# Bordnetzwandler.net
KiCad netlist of a schematic drawn in EAGLE
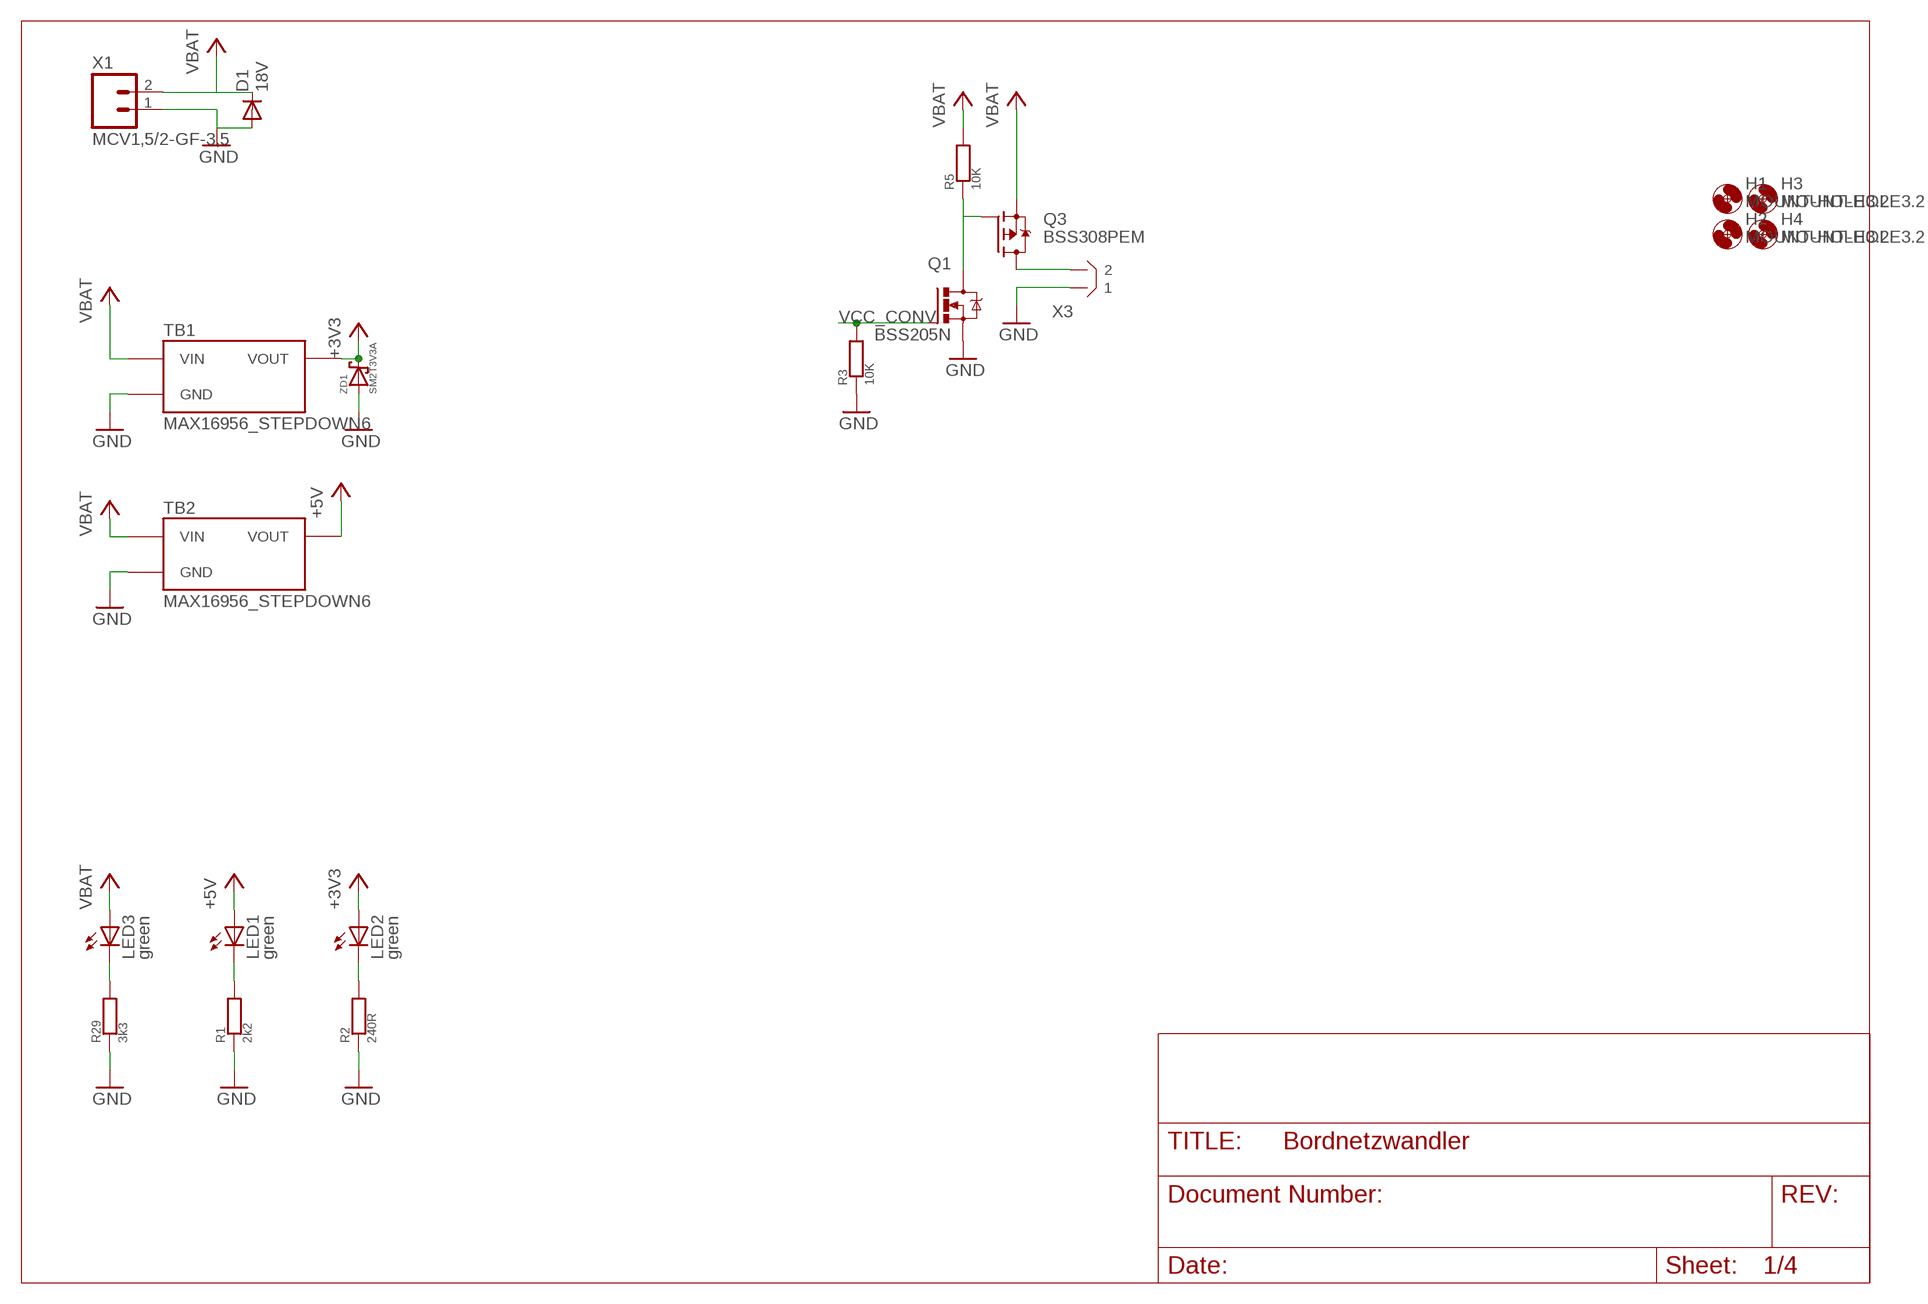
[diagram p0: schematic, sheet 1]
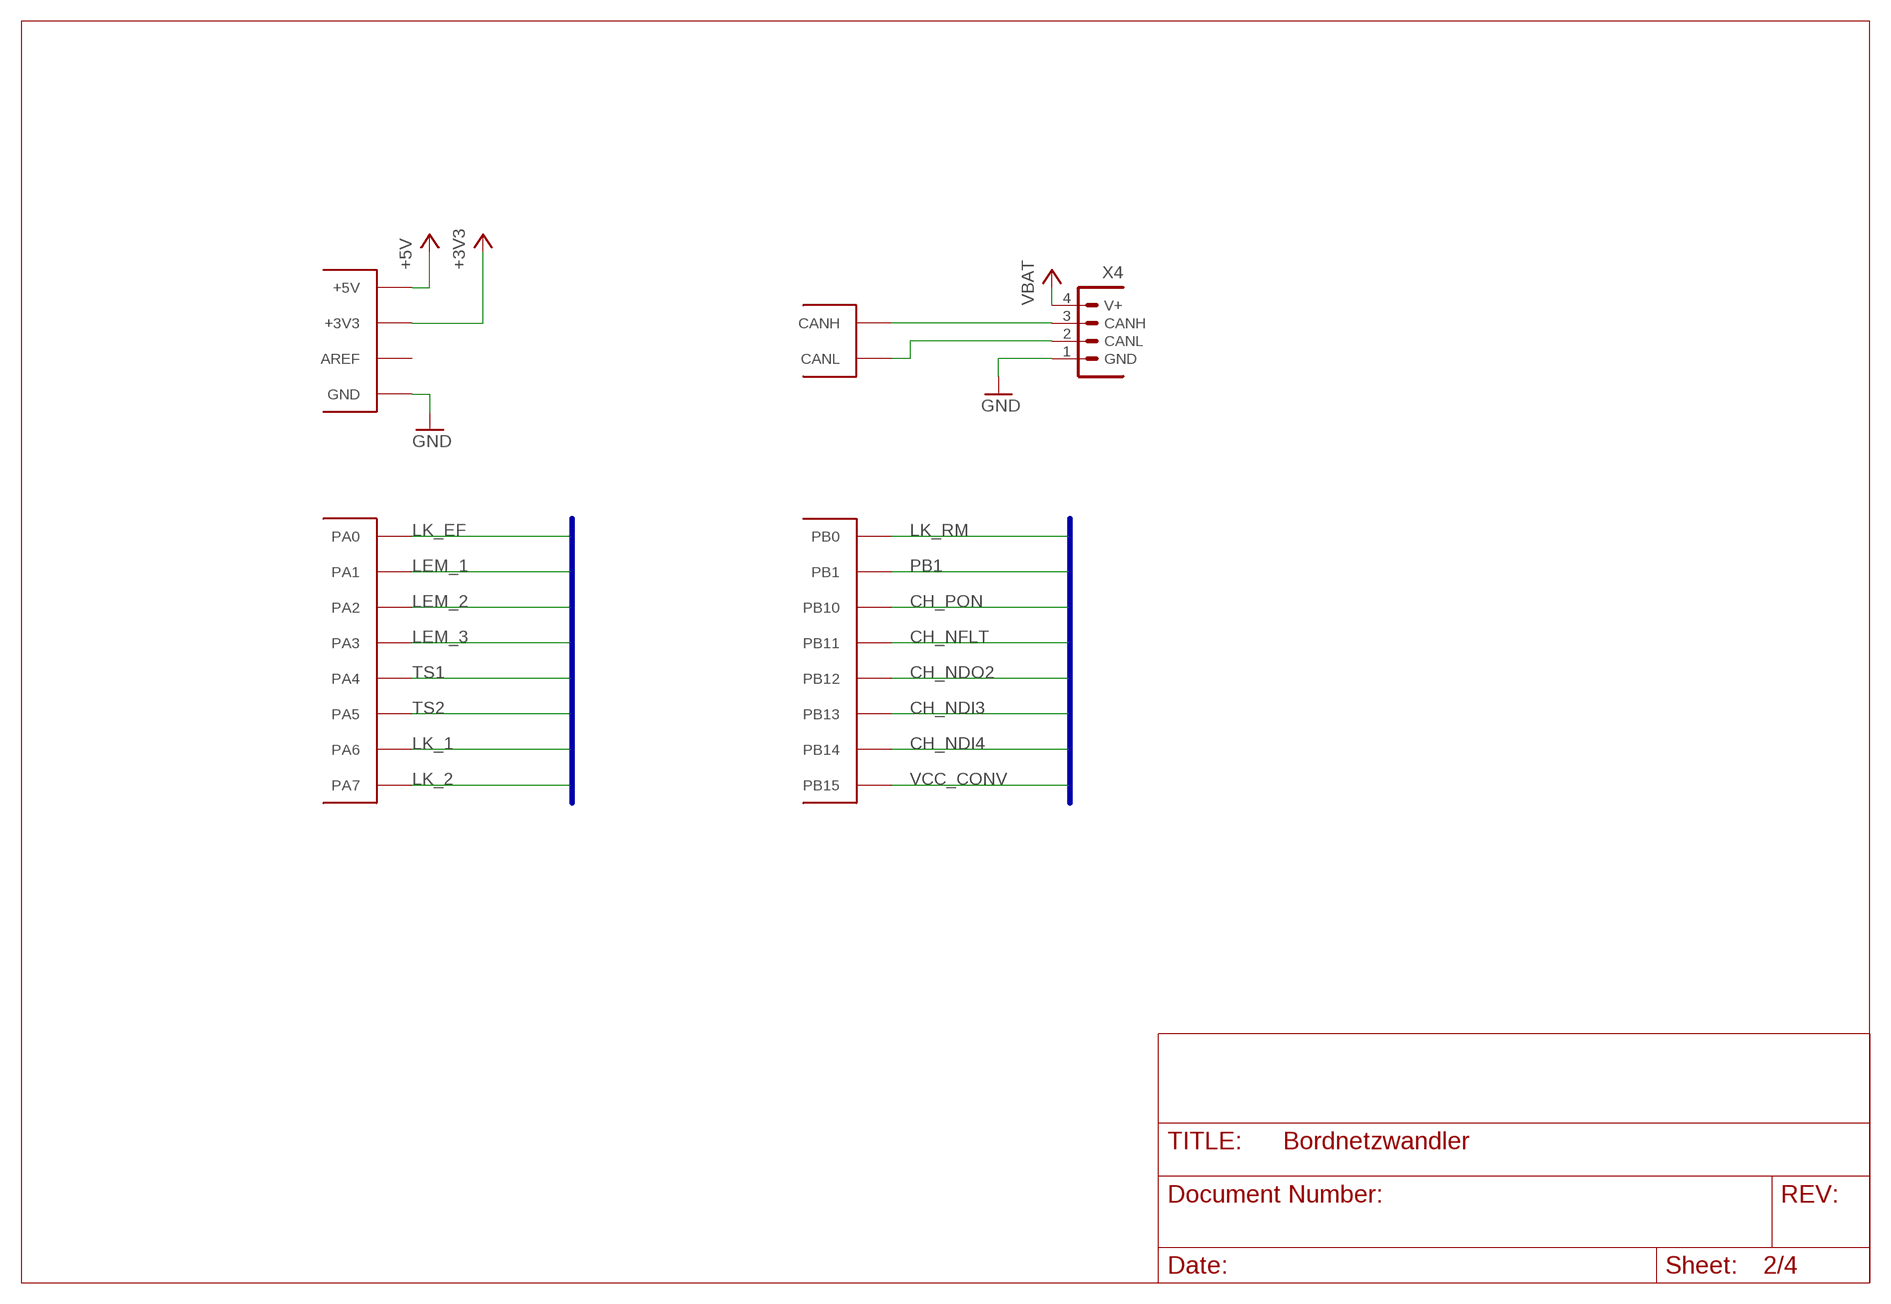
[diagram p1: schematic, sheet 2]
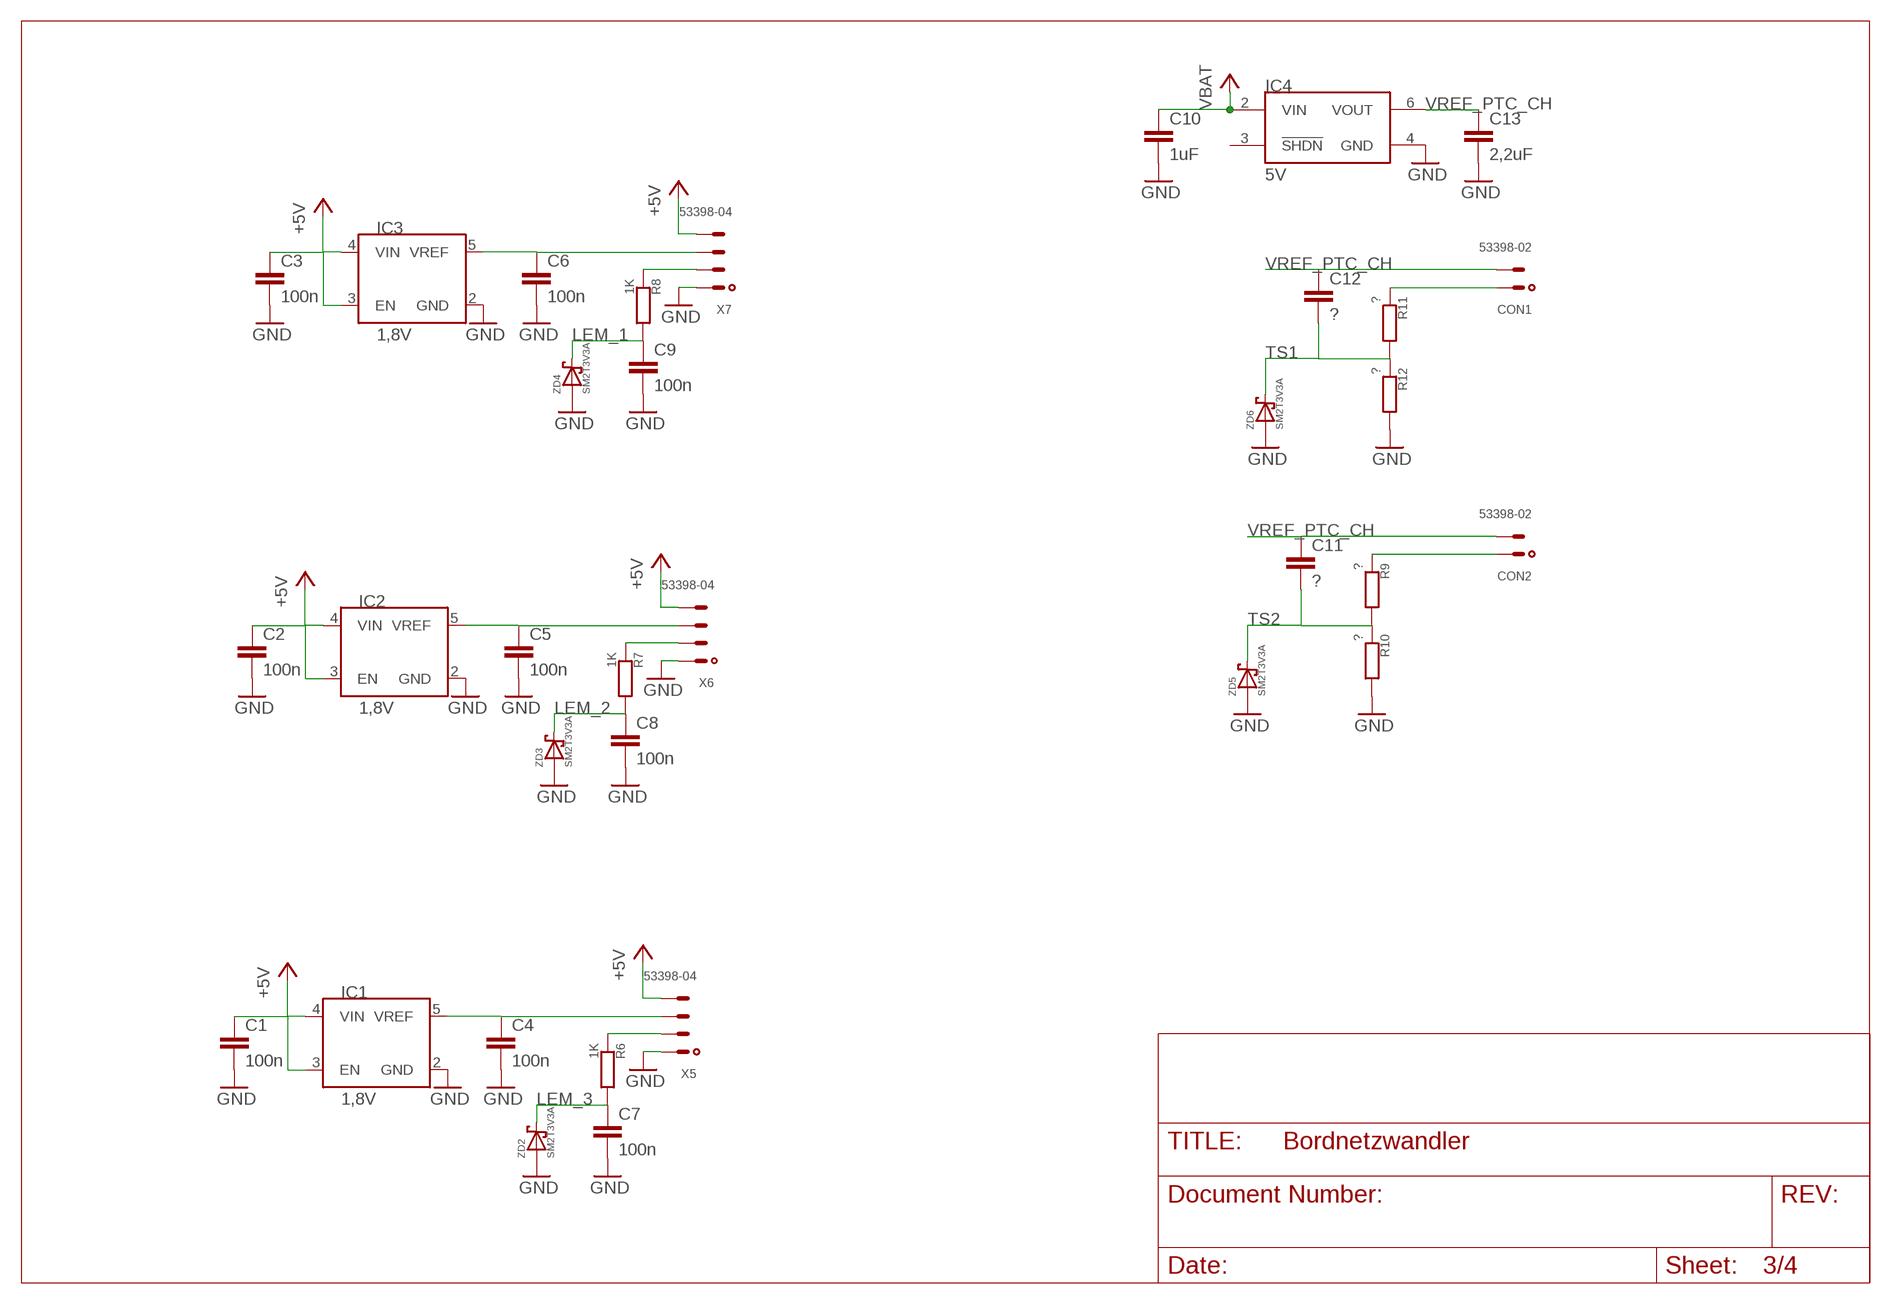
[diagram p2: schematic, sheet 3]
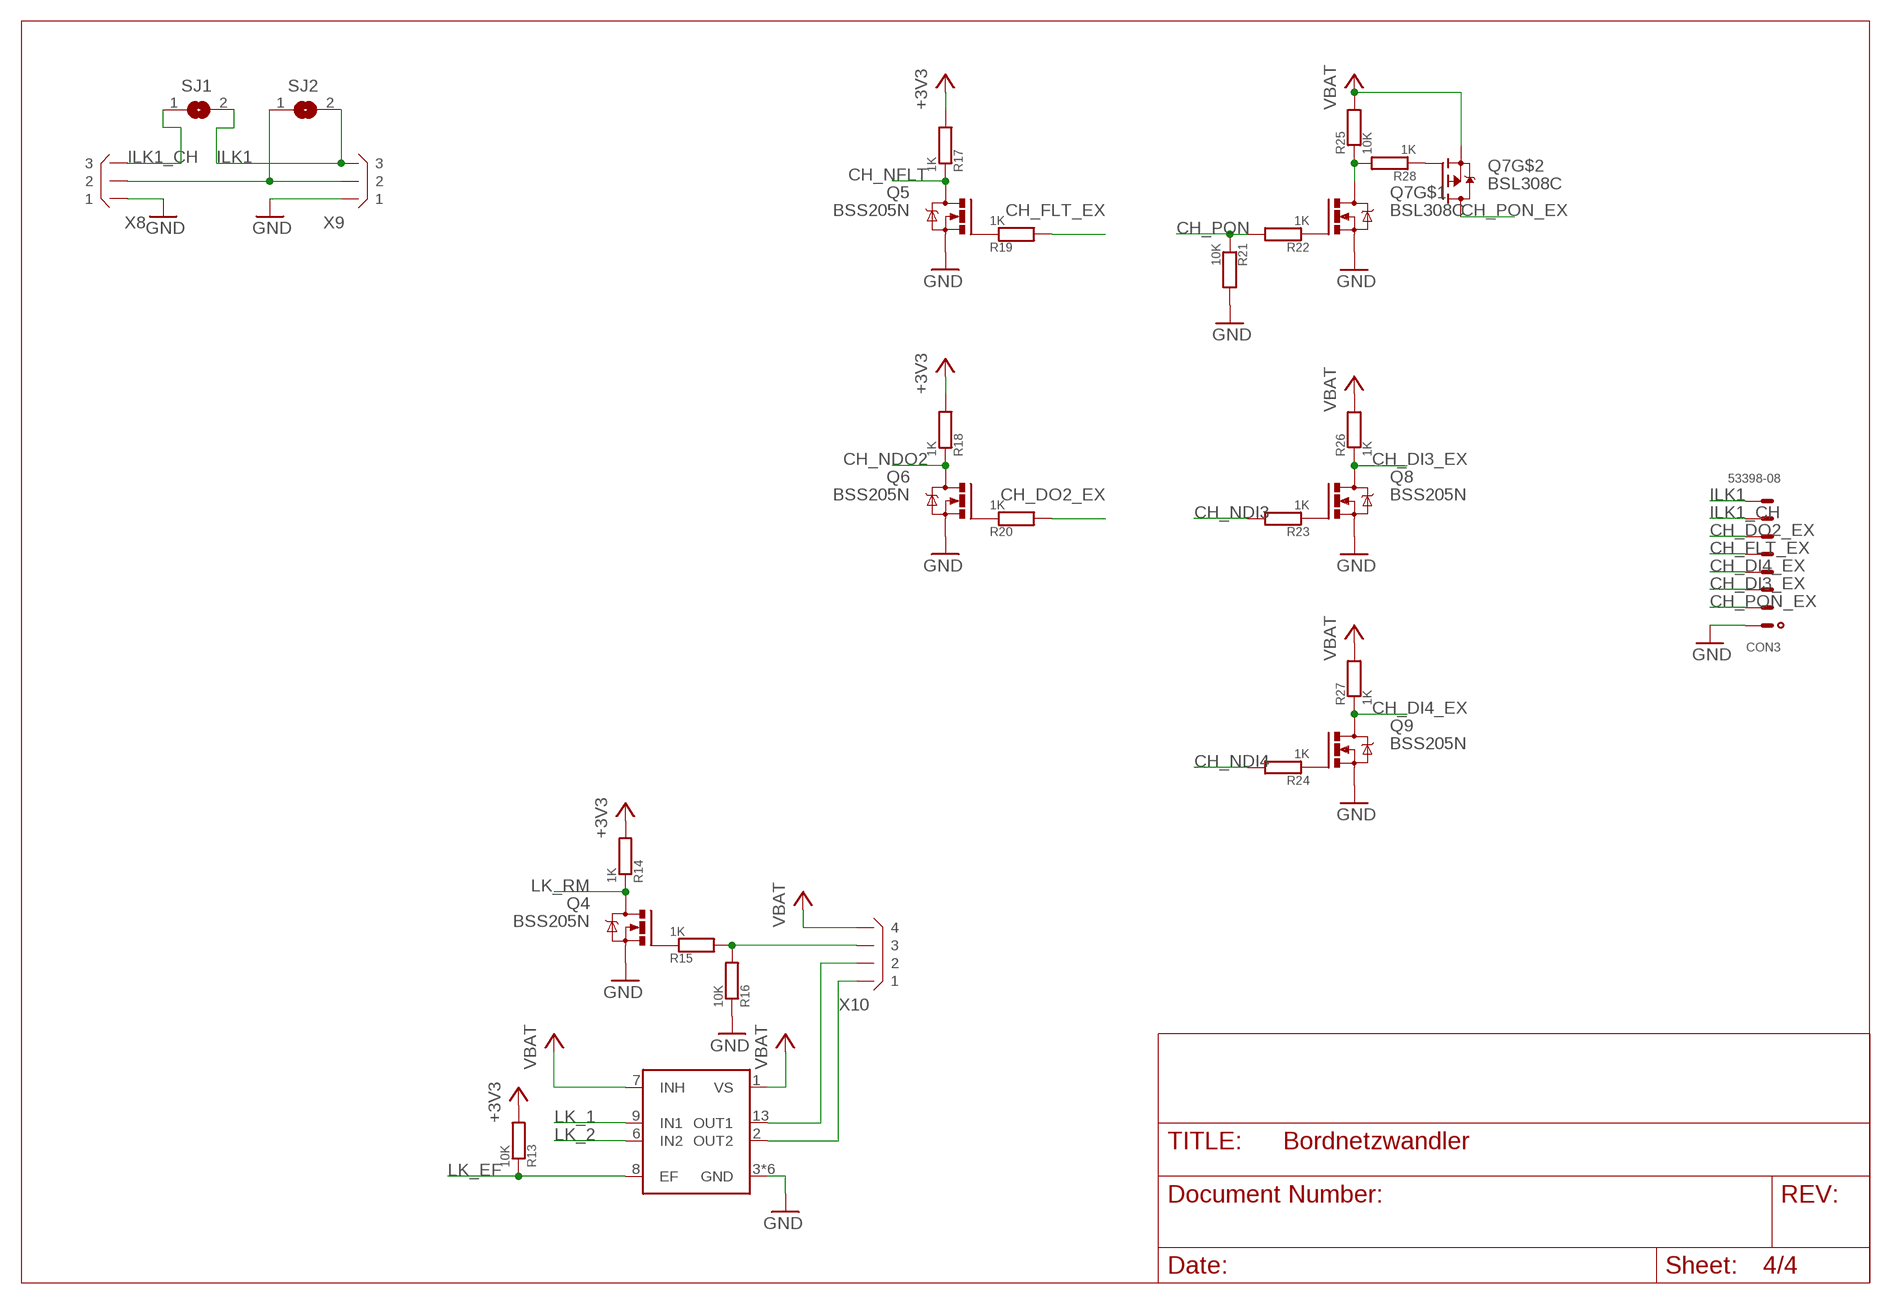
[diagram p3: schematic, sheet 4]

(export (version "E")
  (design (tool "Eeschema 10.0.6"))
  (components
    (comp (ref "D1")
      (value "18V")
      (footprint "eagle-import:DO214AA")
      (libsource (lib "eagle-import") (part "DIODE-DO214AA"))
    )
    (comp (ref "H1")
      (value "MOUNT-HOLE3.2")
      (footprint "eagle-import:3,2")
      (libsource (lib "eagle-import") (part "MOUNT-HOLE3.2"))
    )
    (comp (ref "H2")
      (value "MOUNT-HOLE3.2")
      (footprint "eagle-import:3,2")
      (libsource (lib "eagle-import") (part "MOUNT-HOLE3.2"))
    )
    (comp (ref "H3")
      (value "MOUNT-HOLE3.2")
      (footprint "eagle-import:3,2")
      (libsource (lib "eagle-import") (part "MOUNT-HOLE3.2"))
    )
    (comp (ref "H4")
      (value "MOUNT-HOLE3.2")
      (footprint "eagle-import:3,2")
      (libsource (lib "eagle-import") (part "MOUNT-HOLE3.2"))
    )
    (comp (ref "LED1")
      (value "green")
      (footprint "eagle-import:CHIP-LED0805")
      (libsource (lib "eagle-import") (part "LEDCHIP-LED0805"))
    )
    (comp (ref "LED2")
      (value "green")
      (footprint "eagle-import:CHIP-LED0805")
      (libsource (lib "eagle-import") (part "LEDCHIP-LED0805"))
    )
    (comp (ref "LED3")
      (value "green")
      (footprint "eagle-import:CHIP-LED0805")
      (libsource (lib "eagle-import") (part "LEDCHIP-LED0805"))
    )
    (comp (ref "Q1")
      (value "BSS205N")
      (footprint "eagle-import:SOT23")
      (libsource (lib "eagle-import") (part "BSS205N"))
    )
    (comp (ref "Q3")
      (value "BSS308PEM")
      (footprint "eagle-import:INF-PG-SOT23_M_1PRIMARY")
      (libsource (lib "eagle-import") (part "BSS308PEM"))
    )
    (comp (ref "R1")
      (value "2k2")
      (footprint "eagle-import:R0805")
      (libsource (lib "eagle-import") (part "R"))
    )
    (comp (ref "R2")
      (value "240R")
      (footprint "eagle-import:R0805")
      (libsource (lib "eagle-import") (part "R"))
    )
    (comp (ref "R3")
      (value "10K")
      (footprint "eagle-import:R0805")
      (libsource (lib "eagle-import") (part "R"))
    )
    (comp (ref "R5")
      (value "10K")
      (footprint "eagle-import:R0805")
      (libsource (lib "eagle-import") (part "R"))
    )
    (comp (ref "R29")
      (value "3k3")
      (footprint "eagle-import:R0805")
      (libsource (lib "eagle-import") (part "R"))
    )
    (comp (ref "TB1")
      (value "MAX16956_STEPDOWN6")
      (footprint "eagle-import:MAX16956_STEPDOWN6")
      (libsource (lib "eagle-import") (part "MAX16956_STEPDOWN6"))
    )
    (comp (ref "TB2")
      (value "MAX16956_STEPDOWN6")
      (footprint "eagle-import:MAX16956_STEPDOWN6")
      (libsource (lib "eagle-import") (part "MAX16956_STEPDOWN6"))
    )
    (comp (ref "X1")
      (value "MCV1,5/2-GF-3,5")
      (footprint "eagle-import:MCV1,5_2-GF-3,5")
      (libsource (lib "eagle-import") (part "MCV1,5/2-GF-3,5"))
    )
    (comp (ref "X3")
      (value "B2B-XH")
      (footprint "eagle-import:B2B-XH")
      (libsource (lib "eagle-import") (part "?2B-XHB"))
    )
    (comp (ref "ZD1")
      (value "SM2T3V3A")
      (footprint "eagle-import:SM2T3V3A")
      (libsource (lib "eagle-import") (part "SM2T3V3A"))
    )
    (comp (ref "C1")
      (value "100n")
      (footprint "eagle-import:C0805")
      (libsource (lib "eagle-import") (part "C-EUC0805"))
    )
    (comp (ref "C2")
      (value "100n")
      (footprint "eagle-import:C0805")
      (libsource (lib "eagle-import") (part "C-EUC0805"))
    )
    (comp (ref "C3")
      (value "100n")
      (footprint "eagle-import:C0805")
      (libsource (lib "eagle-import") (part "C-EUC0805"))
    )
    (comp (ref "C4")
      (value "100n")
      (footprint "eagle-import:C0805")
      (libsource (lib "eagle-import") (part "C-EUC0805"))
    )
    (comp (ref "C5")
      (value "100n")
      (footprint "eagle-import:C0805")
      (libsource (lib "eagle-import") (part "C-EUC0805"))
    )
    (comp (ref "C6")
      (value "100n")
      (footprint "eagle-import:C0805")
      (libsource (lib "eagle-import") (part "C-EUC0805"))
    )
    (comp (ref "C7")
      (value "100n")
      (footprint "eagle-import:C0805")
      (libsource (lib "eagle-import") (part "C-EUC0805"))
    )
    (comp (ref "C8")
      (value "100n")
      (footprint "eagle-import:C0805")
      (libsource (lib "eagle-import") (part "C-EUC0805"))
    )
    (comp (ref "C9")
      (value "100n")
      (footprint "eagle-import:C0805")
      (libsource (lib "eagle-import") (part "C-EUC0805"))
    )
    (comp (ref "C10")
      (value "1uF")
      (footprint "eagle-import:C0805")
      (libsource (lib "eagle-import") (part "C-EUC0805"))
    )
    (comp (ref "C11")
      (value "?")
      (footprint "eagle-import:C0805")
      (libsource (lib "eagle-import") (part "C-EUC0805"))
    )
    (comp (ref "C12")
      (value "?")
      (footprint "eagle-import:C0805")
      (libsource (lib "eagle-import") (part "C-EUC0805"))
    )
    (comp (ref "C13")
      (value "2,2uF")
      (footprint "eagle-import:C0805")
      (libsource (lib "eagle-import") (part "C-EUC0805"))
    )
    (comp (ref "CON1")
      (value "53398-02")
      (footprint "eagle-import:53398-02")
      (libsource (lib "eagle-import") (part "53?-02398"))
    )
    (comp (ref "CON2")
      (value "53398-02")
      (footprint "eagle-import:53398-02")
      (libsource (lib "eagle-import") (part "53?-02398"))
    )
    (comp (ref "IC1")
      (value "1,8V")
      (footprint "eagle-import:SOT23-5L")
      (libsource (lib "eagle-import") (part "LM4132L"))
    )
    (comp (ref "IC2")
      (value "1,8V")
      (footprint "eagle-import:SOT23-5L")
      (libsource (lib "eagle-import") (part "LM4132L"))
    )
    (comp (ref "IC3")
      (value "1,8V")
      (footprint "eagle-import:SOT23-5L")
      (libsource (lib "eagle-import") (part "LM4132L"))
    )
    (comp (ref "IC4")
      (value "5V")
      (footprint "eagle-import:SO08")
      (libsource (lib "eagle-import") (part "LT1461"))
    )
    (comp (ref "R6")
      (value "1K")
      (footprint "eagle-import:R0805")
      (libsource (lib "eagle-import") (part "R"))
    )
    (comp (ref "R7")
      (value "1K")
      (footprint "eagle-import:R0805")
      (libsource (lib "eagle-import") (part "R"))
    )
    (comp (ref "R8")
      (value "1K")
      (footprint "eagle-import:R0805")
      (libsource (lib "eagle-import") (part "R"))
    )
    (comp (ref "R9") (value "?") (footprint "eagle-import:R0805") (libsource (lib "eagle-import") (part "R")))
    (comp (ref "R10")
      (value "?")
      (footprint "eagle-import:R0805")
      (libsource (lib "eagle-import") (part "R"))
    )
    (comp (ref "R11")
      (value "?")
      (footprint "eagle-import:R0805")
      (libsource (lib "eagle-import") (part "R"))
    )
    (comp (ref "R12")
      (value "?")
      (footprint "eagle-import:R0805")
      (libsource (lib "eagle-import") (part "R"))
    )
    (comp (ref "X5")
      (value "53398-04")
      (footprint "eagle-import:53398-04")
      (libsource (lib "eagle-import") (part "53?-04398"))
    )
    (comp (ref "X6")
      (value "53398-04")
      (footprint "eagle-import:53398-04")
      (libsource (lib "eagle-import") (part "53?-04398"))
    )
    (comp (ref "X7")
      (value "53398-04")
      (footprint "eagle-import:53398-04")
      (libsource (lib "eagle-import") (part "53?-04398"))
    )
    (comp (ref "ZD2")
      (value "SM2T3V3A")
      (footprint "eagle-import:SM2T3V3A")
      (libsource (lib "eagle-import") (part "SM2T3V3A"))
    )
    (comp (ref "ZD3")
      (value "SM2T3V3A")
      (footprint "eagle-import:SM2T3V3A")
      (libsource (lib "eagle-import") (part "SM2T3V3A"))
    )
    (comp (ref "ZD4")
      (value "SM2T3V3A")
      (footprint "eagle-import:SM2T3V3A")
      (libsource (lib "eagle-import") (part "SM2T3V3A"))
    )
    (comp (ref "ZD5")
      (value "SM2T3V3A")
      (footprint "eagle-import:SM2T3V3A")
      (libsource (lib "eagle-import") (part "SM2T3V3A"))
    )
    (comp (ref "ZD6")
      (value "SM2T3V3A")
      (footprint "eagle-import:SM2T3V3A")
      (libsource (lib "eagle-import") (part "SM2T3V3A"))
    )
    (comp (ref "CON3")
      (value "53398-08")
      (footprint "eagle-import:53398-08")
      (libsource (lib "eagle-import") (part "53?-08398"))
    )
    (comp (ref "IC5")
      (value "TLE4207GN")
      (footprint "eagle-import:INF-PG-DSO-14-22_N_1PRIMARY")
      (libsource (lib "eagle-import") (part "TLE4207GN"))
    )
    (comp (ref "Q4")
      (value "BSS205N")
      (footprint "eagle-import:SOT23")
      (libsource (lib "eagle-import") (part "BSS205N"))
    )
    (comp (ref "Q5")
      (value "BSS205N")
      (footprint "eagle-import:SOT23")
      (libsource (lib "eagle-import") (part "BSS205N"))
    )
    (comp (ref "Q6")
      (value "BSS205N")
      (footprint "eagle-import:SOT23")
      (libsource (lib "eagle-import") (part "BSS205N"))
    )
    (comp (ref "Q7")
      (value "BSL308C")
      (footprint "eagle-import:TSOP-6")
      (libsource (lib "eagle-import") (part "BSL308C"))
    )
    (comp (ref "Q8")
      (value "BSS205N")
      (footprint "eagle-import:SOT23")
      (libsource (lib "eagle-import") (part "BSS205N"))
    )
    (comp (ref "Q9")
      (value "BSS205N")
      (footprint "eagle-import:SOT23")
      (libsource (lib "eagle-import") (part "BSS205N"))
    )
    (comp (ref "R13")
      (value "10K")
      (footprint "eagle-import:R0805")
      (libsource (lib "eagle-import") (part "R"))
    )
    (comp (ref "R14")
      (value "1K")
      (footprint "eagle-import:R0805")
      (libsource (lib "eagle-import") (part "R"))
    )
    (comp (ref "R15")
      (value "1K")
      (footprint "eagle-import:R0805")
      (libsource (lib "eagle-import") (part "R"))
    )
    (comp (ref "R16")
      (value "10K")
      (footprint "eagle-import:R0805")
      (libsource (lib "eagle-import") (part "R"))
    )
    (comp (ref "R17")
      (value "1K")
      (footprint "eagle-import:R0603")
      (libsource (lib "eagle-import") (part "R0603"))
    )
    (comp (ref "R18")
      (value "1K")
      (footprint "eagle-import:R0603")
      (libsource (lib "eagle-import") (part "R0603"))
    )
    (comp (ref "R19")
      (value "1K")
      (footprint "eagle-import:R0603")
      (libsource (lib "eagle-import") (part "R0603"))
    )
    (comp (ref "R20")
      (value "1K")
      (footprint "eagle-import:R0603")
      (libsource (lib "eagle-import") (part "R0603"))
    )
    (comp (ref "R21")
      (value "10K")
      (footprint "eagle-import:R0603")
      (libsource (lib "eagle-import") (part "R0603"))
    )
    (comp (ref "R22")
      (value "1K")
      (footprint "eagle-import:R0603")
      (libsource (lib "eagle-import") (part "R0603"))
    )
    (comp (ref "R23")
      (value "1K")
      (footprint "eagle-import:R0603")
      (libsource (lib "eagle-import") (part "R0603"))
    )
    (comp (ref "R24")
      (value "1K")
      (footprint "eagle-import:R0603")
      (libsource (lib "eagle-import") (part "R0603"))
    )
    (comp (ref "R25")
      (value "10K")
      (footprint "eagle-import:R0603")
      (libsource (lib "eagle-import") (part "R0603"))
    )
    (comp (ref "R26")
      (value "1K")
      (footprint "eagle-import:R0603")
      (libsource (lib "eagle-import") (part "R0603"))
    )
    (comp (ref "R27")
      (value "1K")
      (footprint "eagle-import:R0603")
      (libsource (lib "eagle-import") (part "R0603"))
    )
    (comp (ref "R28")
      (value "1K")
      (footprint "eagle-import:R0603")
      (libsource (lib "eagle-import") (part "R0603"))
    )
    (comp (ref "SJ1") (value "SJ") (footprint "eagle-import:SJ") (libsource (lib "eagle-import") (part "SJ")))
    (comp (ref "SJ2") (value "SJ") (footprint "eagle-import:SJ") (libsource (lib "eagle-import") (part "SJ")))
    (comp (ref "X8")
      (value "B3B-XH")
      (footprint "eagle-import:B3B-XH")
      (libsource (lib "eagle-import") (part "?3B-XHB"))
    )
    (comp (ref "X9")
      (value "B3B-XH")
      (footprint "eagle-import:B3B-XH")
      (libsource (lib "eagle-import") (part "?3B-XHB"))
    )
    (comp (ref "X10")
      (value "B4B-XH")
      (footprint "eagle-import:B4B-XH")
      (libsource (lib "eagle-import") (part "?4B-XHB"))
    )
    (comp (ref "CANIO_1")
      (value "STM32F103XX_CAN-IO-EXPANDER")
      (footprint "eagle-import:STM32F103XX_CANIO-EXPANDER")
      (libsource (lib "eagle-import") (part "STM32F103XX_CAN-IO-EXPANDER"))
    )
    (comp (ref "X4")
      (value "CIOC_4-1-FV-A_CAN-BELEGUNG")
      (footprint "eagle-import:CIOC_4-1-FV")
      (libsource (lib "eagle-import") (part "CIOC_4-1-FV-A_CAN-BELEGUNG"))
    )
  )
  (nets
    (net (code "1") (name "+3V3") (class "Default")
      (node (ref "CANIO_1") (pin "VCC") (pinfunction "+3V3_VCC") (pintype "power_in"))
      (node (ref "LED2") (pin "A") (pinfunction "A_A") (pintype "passive"))
      (node (ref "R13") (pin "2") (pinfunction "2_2") (pintype "passive"))
      (node (ref "R14") (pin "2") (pinfunction "2_2") (pintype "passive"))
      (node (ref "R17") (pin "2") (pinfunction "2_2") (pintype "passive"))
      (node (ref "R18") (pin "2") (pinfunction "2_2") (pintype "passive"))
      (node (ref "TB1") (pin "VOUT") (pinfunction "VOUT_VOUT") (pintype "passive"))
      (node (ref "ZD1") (pin "P$2") (pinfunction "P$2_P$2") (pintype "bidirectional"))
    )
    (net (code "2") (name "+5V") (class "Default")
      (node (ref "C1") (pin "1") (pinfunction "1_1") (pintype "passive"))
      (node (ref "C2") (pin "1") (pinfunction "1_1") (pintype "passive"))
      (node (ref "C3") (pin "1") (pinfunction "1_1") (pintype "passive"))
      (node (ref "CANIO_1") (pin "+5V") (pinfunction "+5V_+5V") (pintype "power_in"))
      (node (ref "IC1") (pin "3") (pinfunction "EN_3") (pintype "bidirectional"))
      (node (ref "IC1") (pin "4") (pinfunction "VIN_4") (pintype "bidirectional"))
      (node (ref "IC2") (pin "3") (pinfunction "EN_3") (pintype "bidirectional"))
      (node (ref "IC2") (pin "4") (pinfunction "VIN_4") (pintype "bidirectional"))
      (node (ref "IC3") (pin "3") (pinfunction "EN_3") (pintype "bidirectional"))
      (node (ref "IC3") (pin "4") (pinfunction "VIN_4") (pintype "bidirectional"))
      (node (ref "LED1") (pin "A") (pinfunction "A_A") (pintype "passive"))
      (node (ref "TB2") (pin "VOUT") (pinfunction "VOUT_VOUT") (pintype "passive"))
      (node (ref "X5") (pin "4") (pinfunction "4_4") (pintype "passive"))
      (node (ref "X6") (pin "4") (pinfunction "4_4") (pintype "passive"))
      (node (ref "X7") (pin "4") (pinfunction "4_4") (pintype "passive"))
    )
    (net (code "3") (name "CH_DI3_EX") (class "Default")
      (node (ref "CON3") (pin "3") (pinfunction "3_3") (pintype "passive"))
      (node (ref "Q8") (pin "3") (pinfunction "D_3") (pintype "passive"))
      (node (ref "R26") (pin "1") (pinfunction "1_1") (pintype "passive"))
    )
    (net (code "4") (name "CH_DI4_EX") (class "Default")
      (node (ref "CON3") (pin "4") (pinfunction "4_4") (pintype "passive"))
      (node (ref "Q9") (pin "3") (pinfunction "D_3") (pintype "passive"))
      (node (ref "R27") (pin "1") (pinfunction "1_1") (pintype "passive"))
    )
    (net (code "5") (name "CH_DO2_EX") (class "Default")
      (node (ref "CON3") (pin "6") (pinfunction "6_6") (pintype "passive"))
      (node (ref "R20") (pin "2") (pinfunction "2_2") (pintype "passive"))
    )
    (net (code "6") (name "CH_FLT_EX") (class "Default")
      (node (ref "CON3") (pin "5") (pinfunction "5_5") (pintype "passive"))
      (node (ref "R19") (pin "2") (pinfunction "2_2") (pintype "passive"))
    )
    (net (code "7") (name "CH_NDI3") (class "Default")
      (node (ref "CANIO_1") (pin "PB13") (pinfunction "PB13_PB13") (pintype "bidirectional"))
      (node (ref "R23") (pin "2") (pinfunction "2_2") (pintype "passive"))
    )
    (net (code "8") (name "CH_NDI4") (class "Default")
      (node (ref "CANIO_1") (pin "PB14") (pinfunction "PB14_PB14") (pintype "bidirectional"))
      (node (ref "R24") (pin "2") (pinfunction "2_2") (pintype "passive"))
    )
    (net (code "9") (name "CH_NDO2") (class "Default")
      (node (ref "CANIO_1") (pin "PB12") (pinfunction "PB12_PB12") (pintype "bidirectional"))
      (node (ref "Q6") (pin "3") (pinfunction "D_3") (pintype "passive"))
      (node (ref "R18") (pin "1") (pinfunction "1_1") (pintype "passive"))
    )
    (net (code "10") (name "CH_NFLT") (class "Default")
      (node (ref "CANIO_1") (pin "PB11") (pinfunction "PB11_PB11") (pintype "bidirectional"))
      (node (ref "Q5") (pin "3") (pinfunction "D_3") (pintype "passive"))
      (node (ref "R17") (pin "1") (pinfunction "1_1") (pintype "passive"))
    )
    (net (code "11") (name "CH_PON") (class "Default")
      (node (ref "CANIO_1") (pin "PB10") (pinfunction "PB10_PB10") (pintype "bidirectional"))
      (node (ref "R21") (pin "1") (pinfunction "1_1") (pintype "passive"))
      (node (ref "R22") (pin "2") (pinfunction "2_2") (pintype "passive"))
    )
    (net (code "12") (name "CH_PON_EX") (class "Default")
      (node (ref "CON3") (pin "2") (pinfunction "2_2") (pintype "passive"))
      (node (ref "Q7") (pin "P$4") (pinfunction "D_P$4") (pintype "passive"))
    )
    (net (code "13") (name "GND") (class "Default")
      (node (ref "C1") (pin "2") (pinfunction "2_2") (pintype "passive"))
      (node (ref "C10") (pin "2") (pinfunction "2_2") (pintype "passive"))
      (node (ref "C13") (pin "2") (pinfunction "2_2") (pintype "passive"))
      (node (ref "C2") (pin "2") (pinfunction "2_2") (pintype "passive"))
      (node (ref "C3") (pin "2") (pinfunction "2_2") (pintype "passive"))
      (node (ref "C4") (pin "2") (pinfunction "2_2") (pintype "passive"))
      (node (ref "C5") (pin "2") (pinfunction "2_2") (pintype "passive"))
      (node (ref "C6") (pin "2") (pinfunction "2_2") (pintype "passive"))
      (node (ref "C7") (pin "2") (pinfunction "2_2") (pintype "passive"))
      (node (ref "C8") (pin "2") (pinfunction "2_2") (pintype "passive"))
      (node (ref "C9") (pin "2") (pinfunction "2_2") (pintype "passive"))
      (node (ref "CANIO_1") (pin "GND1") (pinfunction "GND_GND1") (pintype "power_in"))
      (node (ref "CON3") (pin "1") (pinfunction "1_1") (pintype "passive"))
      (node (ref "D1") (pin "A") (pinfunction "A_A") (pintype "passive"))
      (node (ref "IC1") (pin "2") (pinfunction "GND_2") (pintype "bidirectional"))
      (node (ref "IC2") (pin "2") (pinfunction "GND_2") (pintype "bidirectional"))
      (node (ref "IC3") (pin "2") (pinfunction "GND_2") (pintype "bidirectional"))
      (node (ref "IC4") (pin "4") (pinfunction "GND_4") (pintype "power_in"))
      (node (ref "IC5") (pin "10") (pinfunction "GND_10") (pintype "bidirectional"))
      (node (ref "IC5") (pin "11") (pinfunction "GND_11") (pintype "bidirectional"))
      (node (ref "IC5") (pin "12") (pinfunction "GND_12") (pintype "bidirectional"))
      (node (ref "IC5") (pin "3") (pinfunction "GND_3") (pintype "bidirectional"))
      (node (ref "IC5") (pin "4") (pinfunction "GND_4") (pintype "bidirectional"))
      (node (ref "IC5") (pin "5") (pinfunction "GND_5") (pintype "bidirectional"))
      (node (ref "Q1") (pin "2") (pinfunction "S_2") (pintype "passive"))
      (node (ref "Q4") (pin "2") (pinfunction "S_2") (pintype "passive"))
      (node (ref "Q5") (pin "2") (pinfunction "S_2") (pintype "passive"))
      (node (ref "Q6") (pin "2") (pinfunction "S_2") (pintype "passive"))
      (node (ref "Q7") (pin "P$5") (pinfunction "S_P$5") (pintype "passive"))
      (node (ref "Q8") (pin "2") (pinfunction "S_2") (pintype "passive"))
      (node (ref "Q9") (pin "2") (pinfunction "S_2") (pintype "passive"))
      (node (ref "R1") (pin "1") (pinfunction "1_1") (pintype "passive"))
      (node (ref "R10") (pin "2") (pinfunction "2_2") (pintype "passive"))
      (node (ref "R12") (pin "2") (pinfunction "2_2") (pintype "passive"))
      (node (ref "R16") (pin "1") (pinfunction "1_1") (pintype "passive"))
      (node (ref "R2") (pin "1") (pinfunction "1_1") (pintype "passive"))
      (node (ref "R21") (pin "2") (pinfunction "2_2") (pintype "passive"))
      (node (ref "R29") (pin "1") (pinfunction "1_1") (pintype "passive"))
      (node (ref "R3") (pin "1") (pinfunction "1_1") (pintype "passive"))
      (node (ref "TB1") (pin "GND") (pinfunction "GND_GND") (pintype "power_in"))
      (node (ref "TB1") (pin "GND2") (pinfunction "GND_GND2") (pintype "power_in"))
      (node (ref "TB2") (pin "GND") (pinfunction "GND_GND") (pintype "power_in"))
      (node (ref "TB2") (pin "GND2") (pinfunction "GND_GND2") (pintype "power_in"))
      (node (ref "X1") (pin "1") (pinfunction "1_1") (pintype "passive"))
      (node (ref "X3") (pin "P$1") (pinfunction "1_P$1") (pintype "bidirectional"))
      (node (ref "X4") (pin "1") (pinfunction "GND_1") (pintype "passive"))
      (node (ref "X5") (pin "1") (pinfunction "1_1") (pintype "passive"))
      (node (ref "X6") (pin "1") (pinfunction "1_1") (pintype "passive"))
      (node (ref "X7") (pin "1") (pinfunction "1_1") (pintype "passive"))
      (node (ref "X8") (pin "P$1") (pinfunction "1_P$1") (pintype "bidirectional"))
      (node (ref "X9") (pin "P$1") (pinfunction "1_P$1") (pintype "bidirectional"))
      (node (ref "ZD1") (pin "P$1") (pinfunction "P$1_P$1") (pintype "bidirectional"))
      (node (ref "ZD1") (pin "P$11") (pinfunction "P$1_P$11") (pintype "bidirectional"))
      (node (ref "ZD2") (pin "P$1") (pinfunction "P$1_P$1") (pintype "bidirectional"))
      (node (ref "ZD2") (pin "P$11") (pinfunction "P$1_P$11") (pintype "bidirectional"))
      (node (ref "ZD3") (pin "P$1") (pinfunction "P$1_P$1") (pintype "bidirectional"))
      (node (ref "ZD3") (pin "P$11") (pinfunction "P$1_P$11") (pintype "bidirectional"))
      (node (ref "ZD4") (pin "P$1") (pinfunction "P$1_P$1") (pintype "bidirectional"))
      (node (ref "ZD4") (pin "P$11") (pinfunction "P$1_P$11") (pintype "bidirectional"))
      (node (ref "ZD5") (pin "P$1") (pinfunction "P$1_P$1") (pintype "bidirectional"))
      (node (ref "ZD5") (pin "P$11") (pinfunction "P$1_P$11") (pintype "bidirectional"))
      (node (ref "ZD6") (pin "P$1") (pinfunction "P$1_P$1") (pintype "bidirectional"))
      (node (ref "ZD6") (pin "P$11") (pinfunction "P$1_P$11") (pintype "bidirectional"))
    )
    (net (code "14") (name "ILK1") (class "Default")
      (node (ref "CON3") (pin "8") (pinfunction "8_8") (pintype "passive"))
      (node (ref "SJ1") (pin "2") (pinfunction "2_2") (pintype "passive"))
      (node (ref "SJ2") (pin "2") (pinfunction "2_2") (pintype "passive"))
      (node (ref "X9") (pin "P$3") (pinfunction "3_P$3") (pintype "bidirectional"))
    )
    (net (code "15") (name "ILK1_CH") (class "Default")
      (node (ref "CON3") (pin "7") (pinfunction "7_7") (pintype "passive"))
      (node (ref "SJ1") (pin "1") (pinfunction "1_1") (pintype "passive"))
      (node (ref "X8") (pin "P$3") (pinfunction "3_P$3") (pintype "bidirectional"))
    )
    (net (code "16") (name "LEM_1") (class "Default")
      (node (ref "C9") (pin "1") (pinfunction "1_1") (pintype "passive"))
      (node (ref "CANIO_1") (pin "PA1") (pinfunction "PA1_PA1") (pintype "bidirectional"))
      (node (ref "R8") (pin "2") (pinfunction "2_2") (pintype "passive"))
      (node (ref "ZD4") (pin "P$2") (pinfunction "P$2_P$2") (pintype "bidirectional"))
    )
    (net (code "17") (name "LEM_2") (class "Default")
      (node (ref "C8") (pin "1") (pinfunction "1_1") (pintype "passive"))
      (node (ref "CANIO_1") (pin "PA2") (pinfunction "PA2_PA2") (pintype "bidirectional"))
      (node (ref "R7") (pin "2") (pinfunction "2_2") (pintype "passive"))
      (node (ref "ZD3") (pin "P$2") (pinfunction "P$2_P$2") (pintype "bidirectional"))
    )
    (net (code "18") (name "LEM_3") (class "Default")
      (node (ref "C7") (pin "1") (pinfunction "1_1") (pintype "passive"))
      (node (ref "CANIO_1") (pin "PA3") (pinfunction "PA3_PA3") (pintype "bidirectional"))
      (node (ref "R6") (pin "2") (pinfunction "2_2") (pintype "passive"))
      (node (ref "ZD2") (pin "P$2") (pinfunction "P$2_P$2") (pintype "bidirectional"))
    )
    (net (code "19") (name "LK_1") (class "Default")
      (node (ref "CANIO_1") (pin "PA6") (pinfunction "PA6_PA6") (pintype "bidirectional"))
      (node (ref "IC5") (pin "9") (pinfunction "IN1_9") (pintype "bidirectional"))
    )
    (net (code "20") (name "LK_2") (class "Default")
      (node (ref "CANIO_1") (pin "PA7") (pinfunction "PA7_PA7") (pintype "bidirectional"))
      (node (ref "IC5") (pin "6") (pinfunction "IN2_6") (pintype "bidirectional"))
    )
    (net (code "21") (name "LK_EF") (class "Default")
      (node (ref "CANIO_1") (pin "PA0") (pinfunction "PA0_PA0") (pintype "bidirectional"))
      (node (ref "IC5") (pin "8") (pinfunction "EF_8") (pintype "bidirectional"))
      (node (ref "R13") (pin "1") (pinfunction "1_1") (pintype "passive"))
    )
    (net (code "22") (name "LK_RM") (class "Default")
      (node (ref "CANIO_1") (pin "PB0") (pinfunction "PB0_PB0") (pintype "bidirectional"))
      (node (ref "Q4") (pin "3") (pinfunction "D_3") (pintype "passive"))
      (node (ref "R14") (pin "1") (pinfunction "1_1") (pintype "passive"))
    )
    (net (code "23") (name "Net-(CON1-Pad1)") (class "Default")
      (node (ref "CON1") (pin "1") (pinfunction "1_1") (pintype "passive"))
      (node (ref "R11") (pin "1") (pinfunction "1_1") (pintype "passive"))
    )
    (net (code "24") (name "Net-(CON2-Pad1)") (class "Default")
      (node (ref "CON2") (pin "1") (pinfunction "1_1") (pintype "passive"))
      (node (ref "R9") (pin "1") (pinfunction "1_1") (pintype "passive"))
    )
    (net (code "25") (name "Net-(IC1-VREF)") (class "Default")
      (node (ref "C4") (pin "1") (pinfunction "1_1") (pintype "passive"))
      (node (ref "IC1") (pin "5") (pinfunction "VREF_5") (pintype "bidirectional"))
      (node (ref "X5") (pin "3") (pinfunction "3_3") (pintype "passive"))
    )
    (net (code "26") (name "Net-(IC2-VREF)") (class "Default")
      (node (ref "C5") (pin "1") (pinfunction "1_1") (pintype "passive"))
      (node (ref "IC2") (pin "5") (pinfunction "VREF_5") (pintype "bidirectional"))
      (node (ref "X6") (pin "3") (pinfunction "3_3") (pintype "passive"))
    )
    (net (code "27") (name "Net-(IC3-VREF)") (class "Default")
      (node (ref "C6") (pin "1") (pinfunction "1_1") (pintype "passive"))
      (node (ref "IC3") (pin "5") (pinfunction "VREF_5") (pintype "bidirectional"))
      (node (ref "X7") (pin "3") (pinfunction "3_3") (pintype "passive"))
    )
    (net (code "28") (name "Net-(IC5-OUT1)") (class "Default")
      (node (ref "IC5") (pin "13") (pinfunction "OUT1_13") (pintype "bidirectional"))
      (node (ref "X10") (pin "P$2") (pinfunction "2_P$2") (pintype "bidirectional"))
    )
    (net (code "29") (name "Net-(IC5-OUT2)") (class "Default")
      (node (ref "IC5") (pin "2") (pinfunction "OUT2_2") (pintype "bidirectional"))
      (node (ref "X10") (pin "P$1") (pinfunction "1_P$1") (pintype "bidirectional"))
    )
    (net (code "30") (name "Net-(LED1-PadC)") (class "Default")
      (node (ref "LED1") (pin "C") (pinfunction "C_C") (pintype "passive"))
      (node (ref "R1") (pin "2") (pinfunction "2_2") (pintype "passive"))
    )
    (net (code "31") (name "Net-(LED2-PadC)") (class "Default")
      (node (ref "LED2") (pin "C") (pinfunction "C_C") (pintype "passive"))
      (node (ref "R2") (pin "2") (pinfunction "2_2") (pintype "passive"))
    )
    (net (code "32") (name "Net-(LED3-PadC)") (class "Default")
      (node (ref "LED3") (pin "C") (pinfunction "C_C") (pintype "passive"))
      (node (ref "R29") (pin "2") (pinfunction "2_2") (pintype "passive"))
    )
    (net (code "33") (name "Net-(Q1-D)") (class "Default")
      (node (ref "Q1") (pin "3") (pinfunction "D_3") (pintype "passive"))
      (node (ref "Q3") (pin "1") (pinfunction "G_1") (pintype "passive"))
      (node (ref "R5") (pin "1") (pinfunction "1_1") (pintype "passive"))
    )
    (net (code "34") (name "Net-(Q3-D)") (class "Default")
      (node (ref "Q3") (pin "3") (pinfunction "D_3") (pintype "passive"))
      (node (ref "X3") (pin "P$2") (pinfunction "2_P$2") (pintype "bidirectional"))
    )
    (net (code "35") (name "Net-(Q4-G)") (class "Default")
      (node (ref "Q4") (pin "1") (pinfunction "G_1") (pintype "passive"))
      (node (ref "R15") (pin "1") (pinfunction "1_1") (pintype "passive"))
    )
    (net (code "36") (name "Net-(Q5-G)") (class "Default")
      (node (ref "Q5") (pin "1") (pinfunction "G_1") (pintype "passive"))
      (node (ref "R19") (pin "1") (pinfunction "1_1") (pintype "passive"))
    )
    (net (code "37") (name "Net-(Q6-G)") (class "Default")
      (node (ref "Q6") (pin "1") (pinfunction "G_1") (pintype "passive"))
      (node (ref "R20") (pin "1") (pinfunction "1_1") (pintype "passive"))
    )
    (net (code "38") (name "Net-(Q7A-D)") (class "Default")
      (node (ref "Q7") (pin "P$6") (pinfunction "D_P$6") (pintype "passive"))
      (node (ref "R25") (pin "1") (pinfunction "1_1") (pintype "passive"))
      (node (ref "R28") (pin "2") (pinfunction "2_2") (pintype "passive"))
    )
    (net (code "39") (name "Net-(Q7A-G)") (class "Default")
      (node (ref "Q7") (pin "P$1") (pinfunction "G_P$1") (pintype "passive"))
      (node (ref "R22") (pin "1") (pinfunction "1_1") (pintype "passive"))
    )
    (net (code "40") (name "Net-(Q7B-G)") (class "Default")
      (node (ref "Q7") (pin "P$3") (pinfunction "G_P$3") (pintype "passive"))
      (node (ref "R28") (pin "1") (pinfunction "1_1") (pintype "passive"))
    )
    (net (code "41") (name "Net-(Q8-G)") (class "Default")
      (node (ref "Q8") (pin "1") (pinfunction "G_1") (pintype "passive"))
      (node (ref "R23") (pin "1") (pinfunction "1_1") (pintype "passive"))
    )
    (net (code "42") (name "Net-(Q9-G)") (class "Default")
      (node (ref "Q9") (pin "1") (pinfunction "G_1") (pintype "passive"))
      (node (ref "R24") (pin "1") (pinfunction "1_1") (pintype "passive"))
    )
    (net (code "43") (name "Net-(R6-Pad1)") (class "Default")
      (node (ref "R6") (pin "1") (pinfunction "1_1") (pintype "passive"))
      (node (ref "X5") (pin "2") (pinfunction "2_2") (pintype "passive"))
    )
    (net (code "44") (name "Net-(R7-Pad1)") (class "Default")
      (node (ref "R7") (pin "1") (pinfunction "1_1") (pintype "passive"))
      (node (ref "X6") (pin "2") (pinfunction "2_2") (pintype "passive"))
    )
    (net (code "45") (name "Net-(R8-Pad1)") (class "Default")
      (node (ref "R8") (pin "1") (pinfunction "1_1") (pintype "passive"))
      (node (ref "X7") (pin "2") (pinfunction "2_2") (pintype "passive"))
    )
    (net (code "46") (name "Net-(X4-CANH)") (class "Default")
      (node (ref "CANIO_1") (pin "CANH") (pinfunction "CANH_CANH") (pintype "bidirectional"))
      (node (ref "X4") (pin "3") (pinfunction "CANH_3") (pintype "passive"))
    )
    (net (code "47") (name "Net-(X4-CANL)") (class "Default")
      (node (ref "CANIO_1") (pin "CANL") (pinfunction "CANL_CANL") (pintype "bidirectional"))
      (node (ref "X4") (pin "2") (pinfunction "CANL_2") (pintype "passive"))
    )
    (net (code "48") (name "Net-(X8-2)") (class "Default")
      (node (ref "SJ2") (pin "1") (pinfunction "1_1") (pintype "passive"))
      (node (ref "X8") (pin "P$2") (pinfunction "2_P$2") (pintype "bidirectional"))
      (node (ref "X9") (pin "P$2") (pinfunction "2_P$2") (pintype "bidirectional"))
    )
    (net (code "49") (name "Net-(X10-3)") (class "Default")
      (node (ref "R15") (pin "2") (pinfunction "2_2") (pintype "passive"))
      (node (ref "R16") (pin "2") (pinfunction "2_2") (pintype "passive"))
      (node (ref "X10") (pin "P$3") (pinfunction "3_P$3") (pintype "bidirectional"))
    )
    (net (code "50") (name "PB1") (class "Default")
      (node (ref "CANIO_1") (pin "PB1") (pinfunction "PB1_PB1") (pintype "bidirectional"))
    )
    (net (code "51") (name "TS1") (class "Default")
      (node (ref "C12") (pin "2") (pinfunction "2_2") (pintype "passive"))
      (node (ref "CANIO_1") (pin "PA4") (pinfunction "PA4_PA4") (pintype "bidirectional"))
      (node (ref "R11") (pin "2") (pinfunction "2_2") (pintype "passive"))
      (node (ref "R12") (pin "1") (pinfunction "1_1") (pintype "passive"))
      (node (ref "ZD6") (pin "P$2") (pinfunction "P$2_P$2") (pintype "bidirectional"))
    )
    (net (code "52") (name "TS2") (class "Default")
      (node (ref "C11") (pin "2") (pinfunction "2_2") (pintype "passive"))
      (node (ref "CANIO_1") (pin "PA5") (pinfunction "PA5_PA5") (pintype "bidirectional"))
      (node (ref "R10") (pin "1") (pinfunction "1_1") (pintype "passive"))
      (node (ref "R9") (pin "2") (pinfunction "2_2") (pintype "passive"))
      (node (ref "ZD5") (pin "P$2") (pinfunction "P$2_P$2") (pintype "bidirectional"))
    )
    (net (code "53") (name "VBAT") (class "Default")
      (node (ref "C10") (pin "1") (pinfunction "1_1") (pintype "passive"))
      (node (ref "D1") (pin "C") (pinfunction "C_C") (pintype "passive"))
      (node (ref "IC4") (pin "2") (pinfunction "VIN_2") (pintype "passive"))
      (node (ref "IC5") (pin "1") (pinfunction "VS_1") (pintype "bidirectional"))
      (node (ref "IC5") (pin "7") (pinfunction "INH_7") (pintype "bidirectional"))
      (node (ref "LED3") (pin "A") (pinfunction "A_A") (pintype "passive"))
      (node (ref "Q3") (pin "2") (pinfunction "S_2") (pintype "passive"))
      (node (ref "Q7") (pin "P$2") (pinfunction "S_P$2") (pintype "passive"))
      (node (ref "R25") (pin "2") (pinfunction "2_2") (pintype "passive"))
      (node (ref "R26") (pin "2") (pinfunction "2_2") (pintype "passive"))
      (node (ref "R27") (pin "2") (pinfunction "2_2") (pintype "passive"))
      (node (ref "R5") (pin "2") (pinfunction "2_2") (pintype "passive"))
      (node (ref "TB1") (pin "VIN") (pinfunction "VIN_VIN") (pintype "passive"))
      (node (ref "TB2") (pin "VIN") (pinfunction "VIN_VIN") (pintype "passive"))
      (node (ref "X1") (pin "2") (pinfunction "2_2") (pintype "passive"))
      (node (ref "X10") (pin "P$4") (pinfunction "4_P$4") (pintype "bidirectional"))
      (node (ref "X4") (pin "4") (pinfunction "V+_4") (pintype "passive"))
    )
    (net (code "54") (name "VCC_CONV") (class "Default")
      (node (ref "CANIO_1") (pin "PB15") (pinfunction "PB15_PB15") (pintype "bidirectional"))
      (node (ref "Q1") (pin "1") (pinfunction "G_1") (pintype "passive"))
      (node (ref "R3") (pin "2") (pinfunction "2_2") (pintype "passive"))
    )
    (net (code "55") (name "VREF_PTC_CH") (class "Default")
      (node (ref "C11") (pin "1") (pinfunction "1_1") (pintype "passive"))
      (node (ref "C12") (pin "1") (pinfunction "1_1") (pintype "passive"))
      (node (ref "C13") (pin "1") (pinfunction "1_1") (pintype "passive"))
      (node (ref "CON1") (pin "2") (pinfunction "2_2") (pintype "passive"))
      (node (ref "CON2") (pin "2") (pinfunction "2_2") (pintype "passive"))
      (node (ref "IC4") (pin "6") (pinfunction "VOUT_6") (pintype "bidirectional"))
    )
    (net (code "56") (name "unconnected-(CANIO_1-PadAREF)") (class "Default")
      (node (ref "CANIO_1") (pin "AREF") (pinfunction "AREF_AREF") (pintype "output"))
    )
    (net (code "57") (name "unconnected-(IC4-~{SHDN}-Pad3)") (class "Default")
      (node (ref "IC4") (pin "3") (pinfunction "~{SHDN}_3") (pintype "passive"))
    )
  )
)
